# PWM.net
KiCad netlist of a schematic drawn in Altium Designer
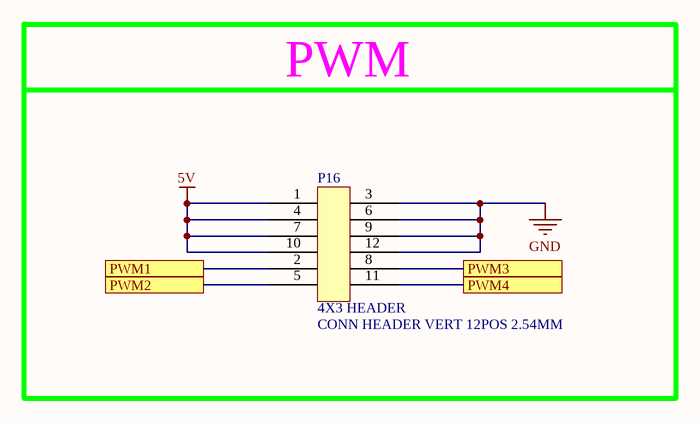
[diagram p0: PWM.SchDoc]

(export (version "E")
  (design (tool "Eeschema 10.0.6"))
  (components
    (comp (ref "P16")
      (value "CONN HEADER VERT 12POS 2.54MM")
      (footprint "TSW-104-23-L-T")
      (libsource (lib "Schlib1") (part "TSW-104-23-L-T"))
    )
  )
  (nets
    (net (code "1") (name "/PWM1") (class "Default") (node (ref "P16") (pin "2") (pintype "passive")))
    (net (code "2") (name "/PWM2") (class "Default") (node (ref "P16") (pin "5") (pintype "passive")))
    (net (code "3") (name "/PWM3") (class "Default") (node (ref "P16") (pin "8") (pintype "passive")))
    (net (code "4") (name "/PWM4") (class "Default") (node (ref "P16") (pin "11") (pintype "passive")))
    (net (code "5") (name "5V") (class "Default")
      (node (ref "P16") (pin "1") (pintype "passive"))
      (node (ref "P16") (pin "10") (pintype "passive"))
      (node (ref "P16") (pin "4") (pintype "passive"))
      (node (ref "P16") (pin "7") (pintype "passive"))
    )
    (net (code "6") (name "GND") (class "Default")
      (node (ref "P16") (pin "12") (pintype "passive"))
      (node (ref "P16") (pin "3") (pintype "passive"))
      (node (ref "P16") (pin "6") (pintype "passive"))
      (node (ref "P16") (pin "9") (pintype "passive"))
    )
  )
)
